# Ethernet_Rev.net
KiCad netlist of a schematic drawn in Altium Designer
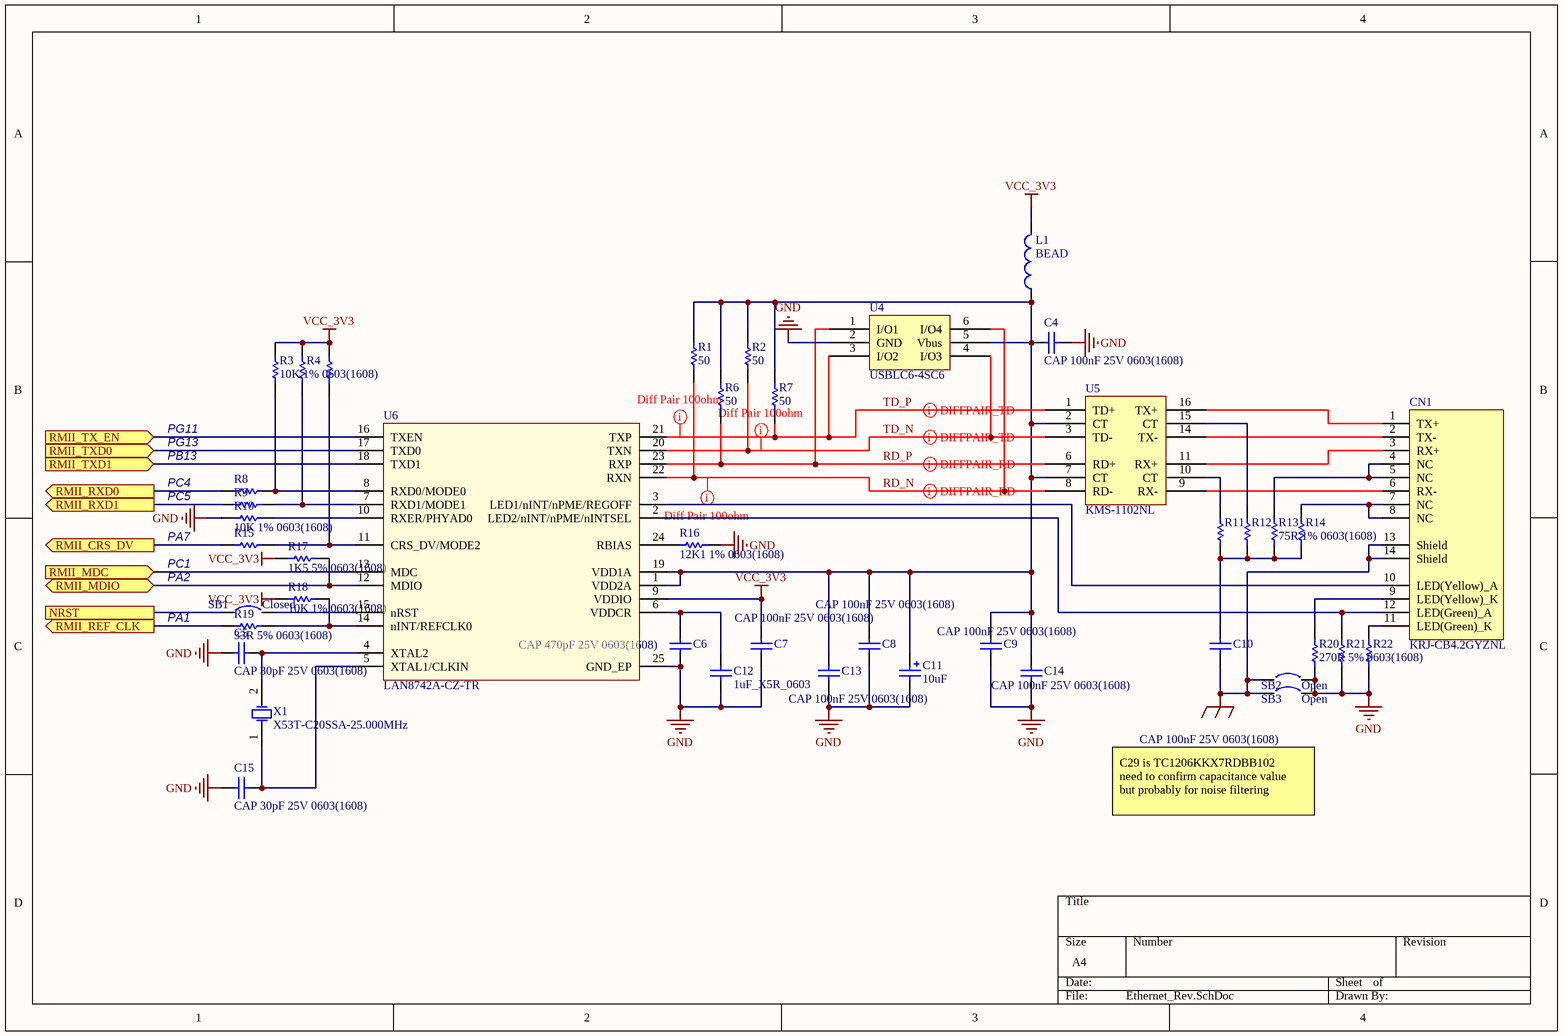
[diagram p0: Ethernet_Rev.SchDoc]

(export (version "E")
  (design (tool "Eeschema 10.0.6"))
  (components
    (comp (ref "C4")
      (value "CAP 100nF 25V 0603(1608)")
      (footprint "CAPC0603(1608)100_N")
      (description "CAP 100nF 25V ±5% 0603 (1608 Metric) Thickness 1mm SMD")
      (fields (field (name "TOLERANCE") "Â±5%"))
      (libsource (lib "Altium Content Vault") (part "CAP"))
    )
    (comp (ref "C5")
      (value "CAP 30pF 25V 0603(1608)")
      (footprint "CAPC0603(1608)100_N")
      (description "CAP 30pF 25V ±5% 0603 (1608 Metric) Thickness 1mm SMD")
      (fields (field (name "TOLERANCE") "Â±5%"))
      (libsource (lib "Altium Content Vault") (part "CAP"))
    )
    (comp (ref "C6")
      (value "CAP 470pF 25V 0603(1608)")
      (footprint "CAPC0603(1608)100_M")
      (description "CAP 470pF 25V ±5% 0603 (1608 Metric) Thickness 1mm SMD")
      (fields (field (name "TOLERANCE") "Â±5%"))
      (libsource (lib "Altium Content Vault") (part "CAP"))
    )
    (comp (ref "C7")
      (value "CAP 100nF 25V 0603(1608)")
      (footprint "CAPC0603(1608)100_N")
      (description "CAP 100nF 25V ±5% 0603 (1608 Metric) Thickness 1mm SMD")
      (fields (field (name "TOLERANCE") "Â±5%"))
      (libsource (lib "Altium Content Vault") (part "CAP"))
    )
    (comp (ref "C8")
      (value "CAP 100nF 25V 0603(1608)")
      (footprint "CAPC0603(1608)100_N")
      (description "CAP 100nF 25V ±5% 0603 (1608 Metric) Thickness 1mm SMD")
      (fields (field (name "TOLERANCE") "Â±5%"))
      (libsource (lib "Altium Content Vault") (part "CAP"))
    )
    (comp (ref "C9")
      (value "CAP 100nF 25V 0603(1608)")
      (footprint "CAPC0603(1608)100_N")
      (description "CAP 100nF 25V ±5% 0603 (1608 Metric) Thickness 1mm SMD")
      (fields (field (name "TOLERANCE") "Â±5%"))
      (libsource (lib "Altium Content Vault") (part "CAP"))
    )
    (comp (ref "C10")
      (value "CAP 100nF 25V 0603(1608)")
      (footprint "CAPC0603(1608)100_N")
      (description "CAP 100nF 25V ±5% 0603 (1608 Metric) Thickness 1mm SMD")
      (fields (field (name "TOLERANCE") "Â±5%"))
      (libsource (lib "Altium Content Vault") (part "CAP"))
    )
    (comp (ref "C11")
      (value "10uF")
      (footprint "TAN-A")
      (description "Polarized Capacitor,10uF,10V,10%,typeA,VISHAY")
      (libsource (lib "MCD_TOOLS") (part "Cap_10uF_POL_10%_TANA"))
    )
    (comp (ref "C12")
      (value "1uF_X5R_0603")
      (footprint "0603C")
      (description "0603  X5R 1µF")
      (fields (field (name "TOLERANCE") "10%"))
      (libsource (lib "MB963_1") (part "CAP SMD 0603  X5R 1µF 25V 10%"))
    )
    (comp (ref "C13")
      (value "CAP 100nF 25V 0603(1608)")
      (footprint "CAPC0603(1608)100_N")
      (description "CAP 100nF 25V ±5% 0603 (1608 Metric) Thickness 1mm SMD")
      (fields (field (name "TOLERANCE") "Â±5%"))
      (libsource (lib "Altium Content Vault") (part "CAP"))
    )
    (comp (ref "C14")
      (value "CAP 100nF 25V 0603(1608)")
      (footprint "CAPC0603(1608)100_N")
      (description "CAP 100nF 25V ±5% 0603 (1608 Metric) Thickness 1mm SMD")
      (fields (field (name "TOLERANCE") "Â±5%"))
      (libsource (lib "Altium Content Vault") (part "CAP"))
    )
    (comp (ref "C15")
      (value "CAP 30pF 25V 0603(1608)")
      (footprint "CAPC0603(1608)100_N")
      (description "CAP 30pF 25V ±5% 0603 (1608 Metric) Thickness 1mm SMD")
      (fields (field (name "TOLERANCE") "Â±5%"))
      (libsource (lib "Altium Content Vault") (part "CAP"))
    )
    (comp (ref "CN1")
      (value "KRJ-CB4.2GYZNL")
      (footprint "RJ45_KRJ-CB4.2GYZNL")
      (description "100 Base-TX (Fast Ethernet) SMD RJ45 single port (1x1) with LEDS Integrated Magnetics Connector")
      (libsource (lib "TAUV_Components") (part "KRJ-CB4.2GYZNL"))
    )
    (comp (ref "L1")
      (value "BEAD")
      (footprint "0603L")
      (description "Inductor")
      (fields (field (name "PUBLISHER") "Altium Limited"))
      (libsource (lib "Miscellaneous Devices") (part "Inductor"))
    )
    (comp (ref "R1")
      (value "50")
      (footprint "0603R")
      (description "Resistor,50,0603,1%,YAGEO")
      (libsource (lib "TAUV_Components") (part "Res_50_1%_0603"))
    )
    (comp (ref "R2")
      (value "50")
      (footprint "0603R")
      (description "Resistor,50,0603,1%,YAGEO")
      (libsource (lib "TAUV_Components") (part "Res_50_1%_0603"))
    )
    (comp (ref "R3")
      (value "10K 1% 0603(1608)")
      (footprint "RESC0603(1608)_N")
      (description "10K 0.1W 1% 0603 (1608 Metric)  SMD")
      (fields (field (name "POWER") "0.1 W") (field (name "TOLERANCE") "1 %"))
      (libsource (lib "Altium Content Vault") (part "RES"))
    )
    (comp (ref "R4")
      (value "10K 1% 0603(1608)")
      (footprint "RESC0603(1608)_N")
      (description "10K 0.1W 1% 0603 (1608 Metric)  SMD")
      (fields (field (name "POWER") "0.1 W") (field (name "TOLERANCE") "1 %"))
      (libsource (lib "Altium Content Vault") (part "RES"))
    )
    (comp (ref "R5")
      (value "10K 1% 0603(1608)")
      (footprint "RESC0603(1608)_N")
      (description "10K 0.1W 1% 0603 (1608 Metric)  SMD")
      (fields (field (name "POWER") "0.1 W") (field (name "TOLERANCE") "1 %"))
      (libsource (lib "Altium Content Vault") (part "RES"))
    )
    (comp (ref "R6")
      (value "50")
      (footprint "0603R")
      (description "Resistor,50,0603,1%,YAGEO")
      (libsource (lib "TAUV_Components") (part "Res_50_1%_0603"))
    )
    (comp (ref "R7")
      (value "50")
      (footprint "0603R")
      (description "Resistor,50,0603,1%,YAGEO")
      (libsource (lib "TAUV_Components") (part "Res_50_1%_0603"))
    )
    (comp (ref "R8")
      (value "33R 5% 0603(1608)")
      (footprint "RESC0603(1608)_M")
      (description "33R 0.1W 5% 0603 (1608 Metric)  SMD")
      (fields (field (name "TOLERANCE") "5 %") (field (name "POWER") "0.1 W"))
      (libsource (lib "Altium Content Vault") (part "RES"))
    )
    (comp (ref "R9")
      (value "33R 5% 0603(1608)")
      (footprint "RESC0603(1608)_M")
      (description "33R 0.1W 5% 0603 (1608 Metric)  SMD")
      (fields (field (name "TOLERANCE") "5 %") (field (name "POWER") "0.1 W"))
      (libsource (lib "Altium Content Vault") (part "RES"))
    )
    (comp (ref "R10")
      (value "10K 1% 0603(1608)")
      (footprint "RESC0603(1608)_N")
      (description "10K 0.1W 1% 0603 (1608 Metric)  SMD")
      (fields (field (name "POWER") "0.1 W") (field (name "TOLERANCE") "1 %"))
      (libsource (lib "Altium Content Vault") (part "RES"))
    )
    (comp (ref "R11")
      (value "75R 1% 0603(1608)")
      (footprint "RESC0603(1608)_M")
      (description "75R 0.1W 1% 0603 (1608 Metric)  SMD")
      (fields (field (name "POWER") "0.1 W") (field (name "TOLERANCE") "1 %"))
      (libsource (lib "Altium Content Vault") (part "RES"))
    )
    (comp (ref "R12")
      (value "75R 1% 0603(1608)")
      (footprint "RESC0603(1608)_M")
      (description "75R 0.1W 1% 0603 (1608 Metric)  SMD")
      (fields (field (name "POWER") "0.1 W") (field (name "TOLERANCE") "1 %"))
      (libsource (lib "Altium Content Vault") (part "RES"))
    )
    (comp (ref "R13")
      (value "75R 1% 0603(1608)")
      (footprint "RESC0603(1608)_M")
      (description "75R 0.1W 1% 0603 (1608 Metric)  SMD")
      (fields (field (name "POWER") "0.1 W") (field (name "TOLERANCE") "1 %"))
      (libsource (lib "Altium Content Vault") (part "RES"))
    )
    (comp (ref "R14")
      (value "75R 1% 0603(1608)")
      (footprint "RESC0603(1608)_M")
      (description "75R 0.1W 1% 0603 (1608 Metric)  SMD")
      (fields (field (name "POWER") "0.1 W") (field (name "TOLERANCE") "1 %"))
      (libsource (lib "Altium Content Vault") (part "RES"))
    )
    (comp (ref "R15")
      (value "33R 5% 0603(1608)")
      (footprint "RESC0603(1608)_M")
      (description "33R 0.1W 5% 0603 (1608 Metric)  SMD")
      (fields (field (name "TOLERANCE") "5 %") (field (name "POWER") "0.1 W"))
      (libsource (lib "Altium Content Vault") (part "RES"))
    )
    (comp (ref "R16")
      (value "12K1 1% 0603(1608)")
      (footprint "RESC0603(1608)_M")
      (description "12K1 0.1W 1% 0603 (1608 Metric)  SMD")
      (fields (field (name "POWER") "0.1 W") (field (name "TOLERANCE") "1 %"))
      (libsource (lib "Altium Content Vault") (part "RES"))
    )
    (comp (ref "R17")
      (value "1K5 5% 0603(1608)")
      (footprint "RESC0603(1608)_M")
      (description "1K5 0.1W 5% 0603 (1608 Metric)  SMD")
      (fields (field (name "POWER") "0.1 W") (field (name "TOLERANCE") "5 %"))
      (libsource (lib "Altium Content Vault") (part "RES"))
    )
    (comp (ref "R18")
      (value "10K 1% 0603(1608)")
      (footprint "RESC0603(1608)_N")
      (description "10K 0.1W 1% 0603 (1608 Metric)  SMD")
      (fields (field (name "POWER") "0.1 W") (field (name "TOLERANCE") "1 %"))
      (libsource (lib "Altium Content Vault") (part "RES"))
    )
    (comp (ref "R19")
      (value "33R 5% 0603(1608)")
      (footprint "RESC0603(1608)_M")
      (description "33R 0.1W 5% 0603 (1608 Metric)  SMD")
      (fields (field (name "TOLERANCE") "5 %") (field (name "POWER") "0.1 W"))
      (libsource (lib "Altium Content Vault") (part "RES"))
    )
    (comp (ref "R20")
      (value "270R 5% 0603(1608)")
      (footprint "RESC0603(1608)_N")
      (description "270R 0.1W 5% 0603 (1608 Metric)  SMD")
      (fields (field (name "POWER") "0.1 W") (field (name "TOLERANCE") "5 %"))
      (libsource (lib "Altium Content Vault") (part "RES"))
    )
    (comp (ref "R21")
      (value "270R 5% 0603(1608)")
      (footprint "RESC0603(1608)_N")
      (description "270R 0.1W 5% 0603 (1608 Metric)  SMD")
      (fields (field (name "POWER") "0.1 W") (field (name "TOLERANCE") "5 %"))
      (libsource (lib "Altium Content Vault") (part "RES"))
    )
    (comp (ref "R22")
      (value "270R 5% 0603(1608)")
      (footprint "RESC0603(1608)_N")
      (description "270R 0.1W 5% 0603 (1608 Metric)  SMD")
      (fields (field (name "POWER") "0.1 W") (field (name "TOLERANCE") "5 %"))
      (libsource (lib "Altium Content Vault") (part "RES"))
    )
    (comp (ref "SB1")
      (value "Closed")
      (footprint "SB_0603")
      (description "Circuit Breaker")
      (fields (field (name "PUBLISHER") "Altium Limited"))
      (libsource (lib "MB1167") (part "Circuit Breaker_close"))
    )
    (comp (ref "SB2")
      (value "Open")
      (footprint "SB_0603")
      (description "Circuit Breaker")
      (fields (field (name "PUBLISHER") "Altium Limited"))
      (libsource (lib "MB1167") (part "Circuit Breaker"))
    )
    (comp (ref "SB3")
      (value "Open")
      (footprint "SB_0603")
      (description "Circuit Breaker")
      (fields (field (name "PUBLISHER") "Altium Limited"))
      (libsource (lib "MB1167") (part "Circuit Breaker"))
    )
    (comp (ref "U4")
      (value "USBLC6-4SC6")
      (footprint "SOT23-6L")
      (libsource (lib "TAUV_Components") (part "USBLC6-4SC6"))
    )
    (comp (ref "U5")
      (value "KMS-1102NL")
      (footprint "Transformer")
      (libsource (lib "TAUV_Components") (part "KMS-1102NL"))
    )
    (comp (ref "U6")
      (value "LAN8742A-CZ-TR")
      (footprint "QFN24_0R5_4X4")
      (libsource (lib "TAUV_Components") (part "LAN8742A-CZ-TR"))
    )
    (comp (ref "X1")
      (value "X53T-C20SSA-25.000MHz")
      (footprint "XTAL_2SM_5R0X3R2")
      (description "Crystal Oscillator")
      (fields (field (name "PUBLISHER") "Altium Limited"))
      (libsource (lib "TAUV_Components") (part "XTAL_5032"))
    )
  )
  (nets
    (net (code "1") (name "/NRST") (class "Default")
      (node (ref "SB1") (pin "1") (pinfunction "1_1") (pintype "passive"))
    )
    (net (code "2") (name "/RD_N") (class "Default")
      (node (ref "R1") (pin "1") (pinfunction "1_1") (pintype "passive"))
      (node (ref "U4") (pin "6") (pinfunction "I/O4_6") (pintype "passive"))
      (node (ref "U5") (pin "8") (pinfunction "RD-_8") (pintype "passive"))
      (node (ref "U6") (pin "22") (pinfunction "RXN_22") (pintype "passive"))
    )
    (net (code "3") (name "/RD_P") (class "Default")
      (node (ref "R6") (pin "1") (pinfunction "1_1") (pintype "passive"))
      (node (ref "U4") (pin "1") (pinfunction "I/O1_1") (pintype "passive"))
      (node (ref "U5") (pin "6") (pinfunction "RD+_6") (pintype "passive"))
      (node (ref "U6") (pin "23") (pinfunction "RXP_23") (pintype "passive"))
    )
    (net (code "4") (name "/RMII_CRS_DV") (class "Default")
      (node (ref "R15") (pin "1") (pinfunction "1_1") (pintype "passive"))
    )
    (net (code "5") (name "/RMII_MDC") (class "Default")
      (node (ref "U6") (pin "13") (pinfunction "MDC_13") (pintype "passive"))
    )
    (net (code "6") (name "/RMII_MDIO") (class "Default")
      (node (ref "R17") (pin "2") (pinfunction "2_2") (pintype "passive"))
      (node (ref "U6") (pin "12") (pinfunction "MDIO_12") (pintype "passive"))
    )
    (net (code "7") (name "/RMII_REF_CLK") (class "Default")
      (node (ref "R19") (pin "1") (pinfunction "1_1") (pintype "passive"))
    )
    (net (code "8") (name "/RMII_RXD0") (class "Default")
      (node (ref "R8") (pin "1") (pinfunction "1_1") (pintype "passive"))
    )
    (net (code "9") (name "/RMII_RXD1") (class "Default")
      (node (ref "R9") (pin "1") (pinfunction "1_1") (pintype "passive"))
    )
    (net (code "10") (name "/RMII_TXD0") (class "Default")
      (node (ref "U6") (pin "17") (pinfunction "TXD0_17") (pintype "passive"))
    )
    (net (code "11") (name "/RMII_TXD1") (class "Default")
      (node (ref "U6") (pin "18") (pinfunction "TXD1_18") (pintype "passive"))
    )
    (net (code "12") (name "/RMII_TX_EN") (class "Default")
      (node (ref "U6") (pin "16") (pinfunction "TXEN_16") (pintype "passive"))
    )
    (net (code "13") (name "/TD_N") (class "Default")
      (node (ref "R2") (pin "1") (pinfunction "1_1") (pintype "passive"))
      (node (ref "U4") (pin "4") (pinfunction "I/O3_4") (pintype "passive"))
      (node (ref "U5") (pin "3") (pinfunction "TD-_3") (pintype "passive"))
      (node (ref "U6") (pin "20") (pinfunction "TXN_20") (pintype "passive"))
    )
    (net (code "14") (name "/TD_P") (class "Default")
      (node (ref "R7") (pin "1") (pinfunction "1_1") (pintype "passive"))
      (node (ref "U4") (pin "3") (pinfunction "I/O2_3") (pintype "passive"))
      (node (ref "U5") (pin "1") (pinfunction "TD+_1") (pintype "passive"))
      (node (ref "U6") (pin "21") (pinfunction "TXP_21") (pintype "passive"))
    )
    (net (code "15") (name "EGND") (class "Default")
      (node (ref "C10") (pin "1") (pinfunction "1_1") (pintype "passive"))
      (node (ref "CN1") (pin "13") (pinfunction "Shield_13") (pintype "passive"))
      (node (ref "CN1") (pin "14") (pinfunction "Shield_14") (pintype "passive"))
      (node (ref "SB2") (pin "1") (pinfunction "1_1") (pintype "passive"))
      (node (ref "SB3") (pin "1") (pinfunction "1_1") (pintype "passive"))
    )
    (net (code "16") (name "GND") (class "Default")
      (node (ref "C11") (pin "2") (pinfunction "2_2") (pintype "passive"))
      (node (ref "C12") (pin "2") (pinfunction "2_2") (pintype "passive"))
      (node (ref "C13") (pin "1") (pinfunction "1_1") (pintype "passive"))
      (node (ref "C14") (pin "1") (pinfunction "1_1") (pintype "passive"))
      (node (ref "C15") (pin "1") (pinfunction "1_1") (pintype "passive"))
      (node (ref "C4") (pin "2") (pinfunction "2_2") (pintype "passive"))
      (node (ref "C5") (pin "1") (pinfunction "1_1") (pintype "passive"))
      (node (ref "C6") (pin "1") (pinfunction "1_1") (pintype "passive"))
      (node (ref "C7") (pin "1") (pinfunction "1_1") (pintype "passive"))
      (node (ref "C8") (pin "1") (pinfunction "1_1") (pintype "passive"))
      (node (ref "C9") (pin "1") (pinfunction "1_1") (pintype "passive"))
      (node (ref "R10") (pin "1") (pinfunction "1_1") (pintype "passive"))
      (node (ref "R16") (pin "2") (pinfunction "2_2") (pintype "passive"))
      (node (ref "R20") (pin "1") (pinfunction "1_1") (pintype "passive"))
      (node (ref "R21") (pin "1") (pinfunction "1_1") (pintype "passive"))
      (node (ref "R22") (pin "1") (pinfunction "1_1") (pintype "passive"))
      (node (ref "SB2") (pin "2") (pinfunction "2_2") (pintype "passive"))
      (node (ref "SB3") (pin "2") (pinfunction "2_2") (pintype "passive"))
      (node (ref "U4") (pin "2") (pinfunction "GND_2") (pintype "passive"))
      (node (ref "U6") (pin "25") (pinfunction "GND_EP_25") (pintype "passive"))
    )
    (net (code "17") (name "Net-(C10-Pad2)") (class "Default")
      (node (ref "C10") (pin "2") (pinfunction "2_2") (pintype "passive"))
      (node (ref "R11") (pin "1") (pinfunction "1_1") (pintype "passive"))
      (node (ref "R12") (pin "1") (pinfunction "1_1") (pintype "passive"))
      (node (ref "R13") (pin "1") (pinfunction "1_1") (pintype "passive"))
      (node (ref "R14") (pin "1") (pinfunction "1_1") (pintype "passive"))
    )
    (net (code "18") (name "Net-(CN1-LED(Green)_A)") (class "Default")
      (node (ref "CN1") (pin "12") (pinfunction "LED(Green)_A_12") (pintype "passive"))
      (node (ref "R21") (pin "2") (pinfunction "2_2") (pintype "passive"))
      (node (ref "U6") (pin "2") (pinfunction "LED2/nINT/nPME/nINTSEL_2") (pintype "passive"))
    )
    (net (code "19") (name "Net-(CN1-LED(Green)_K)") (class "Default")
      (node (ref "CN1") (pin "11") (pinfunction "LED(Green)_K_11") (pintype "passive"))
      (node (ref "R22") (pin "2") (pinfunction "2_2") (pintype "passive"))
    )
    (net (code "20") (name "Net-(CN1-LED(Yellow)_A)") (class "Default")
      (node (ref "CN1") (pin "10") (pinfunction "LED(Yellow)_A_10") (pintype "passive"))
      (node (ref "U6") (pin "3") (pinfunction "LED1/nINT/nPME/REGOFF_3") (pintype "passive"))
    )
    (net (code "21") (name "Net-(CN1-LED(Yellow)_K)") (class "Default")
      (node (ref "CN1") (pin "9") (pinfunction "LED(Yellow)_K_9") (pintype "passive"))
      (node (ref "R20") (pin "2") (pinfunction "2_2") (pintype "passive"))
    )
    (net (code "22") (name "Net-(CN1-NC-Pad4)") (class "Default")
      (node (ref "CN1") (pin "4") (pinfunction "NC_4") (pintype "passive"))
      (node (ref "CN1") (pin "5") (pinfunction "NC_5") (pintype "passive"))
      (node (ref "R13") (pin "2") (pinfunction "2_2") (pintype "passive"))
    )
    (net (code "23") (name "Net-(CN1-NC-Pad7)") (class "Default")
      (node (ref "CN1") (pin "7") (pinfunction "NC_7") (pintype "passive"))
      (node (ref "CN1") (pin "8") (pinfunction "NC_8") (pintype "passive"))
      (node (ref "R14") (pin "2") (pinfunction "2_2") (pintype "passive"))
    )
    (net (code "24") (name "Net-(CN1-RX+)") (class "Default")
      (node (ref "CN1") (pin "3") (pinfunction "RX+_3") (pintype "passive"))
      (node (ref "U5") (pin "11") (pinfunction "RX+_11") (pintype "passive"))
    )
    (net (code "25") (name "Net-(CN1-RX-)") (class "Default")
      (node (ref "CN1") (pin "6") (pinfunction "RX-_6") (pintype "passive"))
      (node (ref "U5") (pin "9") (pinfunction "RX-_9") (pintype "passive"))
    )
    (net (code "26") (name "Net-(CN1-TX+)") (class "Default")
      (node (ref "CN1") (pin "1") (pinfunction "TX+_1") (pintype "passive"))
      (node (ref "U5") (pin "16") (pinfunction "TX+_16") (pintype "passive"))
    )
    (net (code "27") (name "Net-(CN1-TX-)") (class "Default")
      (node (ref "CN1") (pin "2") (pinfunction "TX-_2") (pintype "passive"))
      (node (ref "U5") (pin "14") (pinfunction "TX-_14") (pintype "passive"))
    )
    (net (code "28") (name "Net-(R11-Pad2)") (class "Default")
      (node (ref "R11") (pin "2") (pinfunction "2_2") (pintype "passive"))
      (node (ref "U5") (pin "10") (pinfunction "CT_10") (pintype "passive"))
    )
    (net (code "29") (name "Net-(R12-Pad2)") (class "Default")
      (node (ref "R12") (pin "2") (pinfunction "2_2") (pintype "passive"))
      (node (ref "U5") (pin "15") (pinfunction "CT_15") (pintype "passive"))
    )
    (net (code "30") (name "Net-(U4-Vbus)") (class "Default")
      (node (ref "C11") (pin "1") (pinfunction "1_1") (pintype "passive"))
      (node (ref "C13") (pin "2") (pinfunction "2_2") (pintype "passive"))
      (node (ref "C14") (pin "2") (pinfunction "2_2") (pintype "passive"))
      (node (ref "C4") (pin "1") (pinfunction "1_1") (pintype "passive"))
      (node (ref "C8") (pin "2") (pinfunction "2_2") (pintype "passive"))
      (node (ref "C9") (pin "2") (pinfunction "2_2") (pintype "passive"))
      (node (ref "L1") (pin "1") (pinfunction "1_1") (pintype "passive"))
      (node (ref "R1") (pin "2") (pinfunction "2_2") (pintype "passive"))
      (node (ref "R2") (pin "2") (pinfunction "2_2") (pintype "passive"))
      (node (ref "R6") (pin "2") (pinfunction "2_2") (pintype "passive"))
      (node (ref "R7") (pin "2") (pinfunction "2_2") (pintype "passive"))
      (node (ref "U4") (pin "5") (pinfunction "Vbus_5") (pintype "passive"))
      (node (ref "U5") (pin "2") (pinfunction "CT_2") (pintype "passive"))
      (node (ref "U5") (pin "7") (pinfunction "CT_7") (pintype "passive"))
      (node (ref "U6") (pin "1") (pinfunction "VDD2A_1") (pintype "passive"))
      (node (ref "U6") (pin "19") (pinfunction "VDD1A_19") (pintype "passive"))
    )
    (net (code "31") (name "Net-(U6-CRS_DV{slash}MODE2)") (class "Default")
      (node (ref "R15") (pin "2") (pinfunction "2_2") (pintype "passive"))
      (node (ref "R5") (pin "1") (pinfunction "1_1") (pintype "passive"))
      (node (ref "U6") (pin "11") (pinfunction "CRS_DV/MODE2_11") (pintype "passive"))
    )
    (net (code "32") (name "Net-(U6-RBIAS)") (class "Default")
      (node (ref "R16") (pin "1") (pinfunction "1_1") (pintype "passive"))
      (node (ref "U6") (pin "24") (pinfunction "RBIAS_24") (pintype "passive"))
    )
    (net (code "33") (name "Net-(U6-RXD0{slash}MODE0)") (class "Default")
      (node (ref "R3") (pin "1") (pinfunction "1_1") (pintype "passive"))
      (node (ref "R8") (pin "2") (pinfunction "2_2") (pintype "passive"))
      (node (ref "U6") (pin "8") (pinfunction "RXD0/MODE0_8") (pintype "passive"))
    )
    (net (code "34") (name "Net-(U6-RXD1{slash}MODE1)") (class "Default")
      (node (ref "R4") (pin "1") (pinfunction "1_1") (pintype "passive"))
      (node (ref "R9") (pin "2") (pinfunction "2_2") (pintype "passive"))
      (node (ref "U6") (pin "7") (pinfunction "RXD1/MODE1_7") (pintype "passive"))
    )
    (net (code "35") (name "Net-(U6-RXER{slash}PHYAD0)") (class "Default")
      (node (ref "R10") (pin "2") (pinfunction "2_2") (pintype "passive"))
      (node (ref "U6") (pin "10") (pinfunction "RXER/PHYAD0_10") (pintype "passive"))
    )
    (net (code "36") (name "Net-(U6-VDDCR)") (class "Default")
      (node (ref "C12") (pin "1") (pinfunction "1_1") (pintype "passive"))
      (node (ref "C6") (pin "2") (pinfunction "2_2") (pintype "passive"))
      (node (ref "U6") (pin "6") (pinfunction "VDDCR_6") (pintype "passive"))
    )
    (net (code "37") (name "Net-(U6-XTAL1{slash}CLKIN)") (class "Default")
      (node (ref "C15") (pin "2") (pinfunction "2_2") (pintype "passive"))
      (node (ref "U6") (pin "5") (pinfunction "XTAL1/CLKIN_5") (pintype "passive"))
      (node (ref "X1") (pin "1") (pinfunction "OSC1_1") (pintype "passive"))
    )
    (net (code "38") (name "Net-(U6-XTAL2)") (class "Default")
      (node (ref "C5") (pin "2") (pinfunction "2_2") (pintype "passive"))
      (node (ref "U6") (pin "4") (pinfunction "XTAL2_4") (pintype "passive"))
      (node (ref "X1") (pin "2") (pinfunction "OSC2_2") (pintype "passive"))
    )
    (net (code "39") (name "Net-(U6-nINT{slash}REFCLK0)") (class "Default")
      (node (ref "R18") (pin "2") (pinfunction "2_2") (pintype "passive"))
      (node (ref "R19") (pin "2") (pinfunction "2_2") (pintype "passive"))
      (node (ref "U6") (pin "14") (pinfunction "nINT/REFCLK0_14") (pintype "passive"))
    )
    (net (code "40") (name "Net-(U6-nRST)") (class "Default")
      (node (ref "SB1") (pin "2") (pinfunction "2_2") (pintype "passive"))
      (node (ref "U6") (pin "15") (pinfunction "nRST_15") (pintype "passive"))
    )
    (net (code "41") (name "VCC_3V3") (class "Default")
      (node (ref "C7") (pin "2") (pinfunction "2_2") (pintype "passive"))
      (node (ref "L1") (pin "2") (pinfunction "2_2") (pintype "passive"))
      (node (ref "R17") (pin "1") (pinfunction "1_1") (pintype "passive"))
      (node (ref "R18") (pin "1") (pinfunction "1_1") (pintype "passive"))
      (node (ref "R3") (pin "2") (pinfunction "2_2") (pintype "passive"))
      (node (ref "R4") (pin "2") (pinfunction "2_2") (pintype "passive"))
      (node (ref "R5") (pin "2") (pinfunction "2_2") (pintype "passive"))
      (node (ref "U6") (pin "9") (pinfunction "VDDIO_9") (pintype "passive"))
    )
  )
)
